# lm317-adjustable.net
KiCad netlist of a schematic drawn in Altium Designer
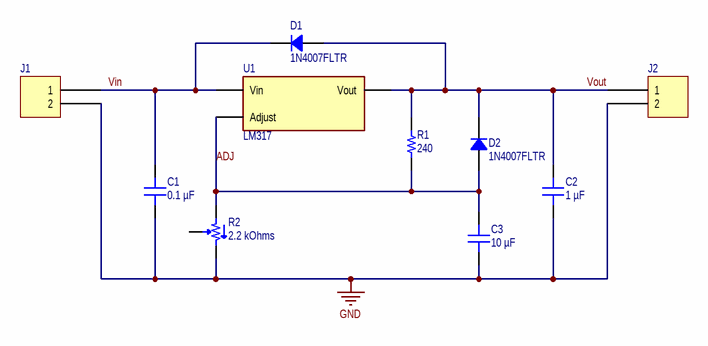
[diagram p0: lm317-adjustable.SchDoc]

(export (version "E")
  (design (tool "Eeschema 10.0.6"))
  (components
    (comp (ref "C1")
      (value "0.1 µF")
      (footprint "CAP 0805_2012")
      (description "CAP CER 0.1UF 50V X7R 0805")
      (fields
        (field (name "PART NUMBER") "CC0805MRX7R9BB104")
        (field (name "CAPACITANCE") "0.1 µF")
        (field (name "MANUFACTURER") "Yageo")
      )
      (libsource (lib "Celestial Altium Library - altium_library") (part "Capacitor"))
    )
    (comp (ref "C2")
      (value "1 µF")
      (footprint "CAP 0805_2012")
      (description "CAP CER 1UF 50V X7R 0805")
      (fields
        (field (name "PART NUMBER") "GCJ21BR71H105KA01L")
        (field (name "CAPACITANCE") "1 µF")
        (field (name "MANUFACTURER") "Murata Electronics")
      )
      (libsource (lib "Celestial Altium Library - altium_library") (part "Capacitor"))
    )
    (comp (ref "C3")
      (value "10 µF")
      (footprint "CAP 0805_2012")
      (description "CAP CER 10UF 25V X5R 0805")
      (fields
        (field (name "PART NUMBER") "GRM21BR61E106MA73L")
        (field (name "CAPACITANCE") "10 µF")
        (field (name "MANUFACTURER") "Murata Electronics")
      )
      (libsource (lib "Celestial Altium Library - altium_library") (part "Capacitor"))
    )
    (comp (ref "D1")
      (value "1N4007FLTR")
      (footprint "SOD123F")
      (description "STANDARD RECTIFIER 1000V SOD-123")
      (fields (field (name "MANUFACTURER") "SMC Diode Solutions"))
      (libsource (lib "Celestial Altium Library - altium_library") (part "Diode"))
    )
    (comp (ref "D2")
      (value "1N4007FLTR")
      (footprint "SOD123F")
      (description "STANDARD RECTIFIER 1000V SOD-123")
      (fields (field (name "MANUFACTURER") "SMC Diode Solutions"))
      (libsource (lib "Celestial Altium Library - altium_library") (part "Diode"))
    )
    (comp (ref "J1")
      (value "282837-2")
      (footprint "TE 282837-2")
      (description "TERM BLK 2P SIDE ENT 5.08MM PCB")
      (fields (field (name "MANUFACTURER") "TE Connectivity AMP Connectors") (field (name "VOLTAGE") "300 V"))
      (libsource (lib "Celestial Altium Library - altium_library") (part "2 Pin"))
    )
    (comp (ref "J2")
      (value "282837-2")
      (footprint "TE 282837-2")
      (description "TERM BLK 2P SIDE ENT 5.08MM PCB")
      (fields (field (name "MANUFACTURER") "TE Connectivity AMP Connectors") (field (name "VOLTAGE") "300 V"))
      (libsource (lib "") (part "2 Pin_1"))
    )
    (comp (ref "R1")
      (value "240")
      (footprint "RES 0805_2012")
      (description "RES SMD 240 OHM 0.5% 1/4W 0805")
      (fields
        (field (name "PART NUMBER") "ERJ-PB6D2400V")
        (field (name "MANUFACTURER") "Panasonic Electronic Components")
      )
      (libsource (lib "Celestial Altium Library - altium_library") (part "Resistor"))
    )
    (comp (ref "R2")
      (value "2.2 kOhms")
      (footprint "POT BOURNS TRIMPOT TC33")
      (description "TRIMMER 2.2K OHM 0.1W J LEAD TOP")
      (fields (field (name "PART NUMBER") "TC33X-J-222E") (field (name "MANUFACTURER") "Bourns Inc."))
      (libsource (lib "Celestial Altium Library - altium_library") (part "Potentiometer"))
    )
    (comp (ref "U1")
      (value "LM317")
      (footprint "FP-369C-MFG")
      (libsource (lib "Altium Content Vault") (part "bee26fb5c311ea5cf4e297f9acd4e99"))
    )
  )
  (nets
    (net (code "1") (name "/ADJ") (class "Default")
      (node (ref "C3") (pin "2") (pinfunction "2_2") (pintype "passive"))
      (node (ref "D2") (pin "1") (pinfunction "1_1") (pintype "passive"))
      (node (ref "R1") (pin "1") (pinfunction "1_1") (pintype "passive"))
      (node (ref "R2") (pin "1") (pinfunction "1_1") (pintype "passive"))
      (node (ref "U1") (pin "1") (pinfunction "Adjust_1") (pintype "passive"))
    )
    (net (code "2") (name "/Vin") (class "Default")
      (node (ref "C1") (pin "2") (pinfunction "2_2") (pintype "passive"))
      (node (ref "D1") (pin "2") (pinfunction "2_2") (pintype "passive"))
      (node (ref "J1") (pin "1") (pinfunction "1_1") (pintype "passive"))
      (node (ref "U1") (pin "3") (pinfunction "Vin_3") (pintype "power_in"))
    )
    (net (code "3") (name "/Vout") (class "Default")
      (node (ref "C2") (pin "2") (pinfunction "2_2") (pintype "passive"))
      (node (ref "D1") (pin "1") (pinfunction "1_1") (pintype "passive"))
      (node (ref "D2") (pin "2") (pinfunction "2_2") (pintype "passive"))
      (node (ref "J2") (pin "1") (pinfunction "1_1") (pintype "passive"))
      (node (ref "R1") (pin "2") (pinfunction "2_2") (pintype "passive"))
      (node (ref "U1") (pin "4") (pinfunction "Vout_4") (pintype "power_in"))
    )
    (net (code "4") (name "GND") (class "Default")
      (node (ref "C1") (pin "1") (pinfunction "1_1") (pintype "passive"))
      (node (ref "C2") (pin "1") (pinfunction "1_1") (pintype "passive"))
      (node (ref "C3") (pin "1") (pinfunction "1_1") (pintype "passive"))
      (node (ref "J1") (pin "2") (pinfunction "2_2") (pintype "passive"))
      (node (ref "J2") (pin "2") (pinfunction "2_2") (pintype "passive"))
      (node (ref "R2") (pin "3") (pinfunction "3_3") (pintype "passive"))
    )
    (net (code "5") (name "unconnected-(R2-Pad2)") (class "Default")
      (node (ref "R2") (pin "2") (pinfunction "2_2") (pintype "passive"))
    )
  )
)
